# schematic.net
KiCad netlist of a schematic drawn in EAGLE
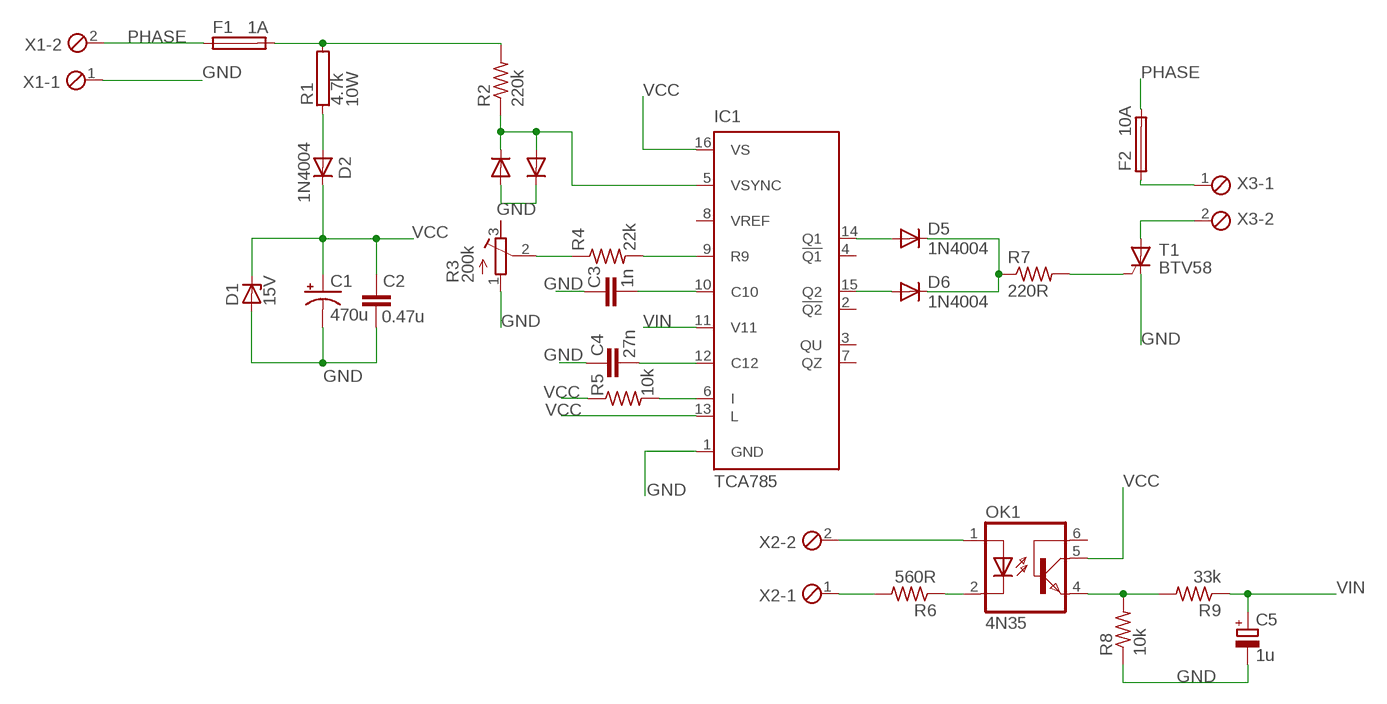
[diagram p0: schematic, sheet 1]

(export (version "E")
  (design (tool "Eeschema 10.0.6"))
  (components
    (comp (ref "C1")
      (value "470u")
      (footprint "eagle-import:E3,5-8")
      (libsource (lib "eagle-import") (part "CPOL-USE3.5-8"))
    )
    (comp (ref "C2")
      (value "0.47u")
      (footprint "eagle-import:C025-025X050")
      (libsource (lib "eagle-import") (part "C-EU025-025X050"))
    )
    (comp (ref "C3")
      (value "1n")
      (footprint "eagle-import:C025-025X050")
      (libsource (lib "eagle-import") (part "C-EU025-025X050"))
    )
    (comp (ref "C4")
      (value "27n")
      (footprint "eagle-import:C025-025X050")
      (libsource (lib "eagle-import") (part "C-EU025-025X050"))
    )
    (comp (ref "C5")
      (value "1u")
      (footprint "eagle-import:E2,5-6E")
      (libsource (lib "eagle-import") (part "CPOL-EUE2,5-6E"))
    )
    (comp (ref "D1")
      (value "15V")
      (footprint "eagle-import:F126Z12")
      (libsource (lib "eagle-import") (part "BZY97"))
    )
    (comp (ref "D2")
      (value "1N4004")
      (footprint "eagle-import:DO41-10")
      (libsource (lib "eagle-import") (part "1N4004"))
    )
    (comp (ref "D3")
      (value "1N4004")
      (footprint "eagle-import:DO41-10")
      (libsource (lib "eagle-import") (part "1N4004"))
    )
    (comp (ref "D4")
      (value "1N4004")
      (footprint "eagle-import:DO41-10")
      (libsource (lib "eagle-import") (part "1N4004"))
    )
    (comp (ref "D5")
      (value "1N4004")
      (footprint "eagle-import:DO41-10")
      (libsource (lib "eagle-import") (part "1N4004"))
    )
    (comp (ref "D6")
      (value "1N4004")
      (footprint "eagle-import:DO41-10")
      (libsource (lib "eagle-import") (part "1N4004"))
    )
    (comp (ref "F1")
      (value "1A")
      (footprint "eagle-import:SH25")
      (fields (field (name "MF") "SCHURTER") (field (name "MPN") "0031.8211"))
      (libsource (lib "eagle-import") (part "SH25"))
    )
    (comp (ref "F2")
      (value "10A")
      (footprint "eagle-import:SH25")
      (fields (field (name "MF") "SCHURTER") (field (name "MPN") "0031.8211"))
      (libsource (lib "eagle-import") (part "SH25"))
    )
    (comp (ref "IC1")
      (value "TCA785")
      (footprint "eagle-import:DIL16")
      (fields (field (name "MF") "Infineon Technologies"))
      (libsource (lib "eagle-import") (part "TCA785"))
    )
    (comp (ref "OK1")
      (value "4N35")
      (footprint "eagle-import:DIL06")
      (fields (field (name "MF") "FAIRCHILD SEMICONDUCTOR"))
      (libsource (lib "eagle-import") (part "4N35"))
    )
    (comp (ref "R1")
      (value "4.7k")
      (footprint "eagle-import:AC10")
      (fields (field (name "P") "10W"))
      (libsource (lib "eagle-import") (part "RAC10"))
    )
    (comp (ref "R2")
      (value "220k")
      (footprint "eagle-import:0207_10")
      (fields (field (name "SPICEPREFIX") "R"))
      (libsource (lib "eagle-import") (part "R-US_0207/10"))
    )
    (comp (ref "R3")
      (value "200k")
      (footprint "eagle-import:RTRIM64W")
      (libsource (lib "eagle-import") (part "R-TRIMM64W"))
    )
    (comp (ref "R4")
      (value "22k")
      (footprint "eagle-import:0207_10")
      (libsource (lib "eagle-import") (part "R-US_0207/10"))
    )
    (comp (ref "R5")
      (value "10k")
      (footprint "eagle-import:0207_15")
      (libsource (lib "eagle-import") (part "R-US_0207/15"))
    )
    (comp (ref "R6")
      (value "560R")
      (footprint "eagle-import:0204_7")
      (libsource (lib "eagle-import") (part "R-US_0204/7"))
    )
    (comp (ref "R7")
      (value "220R")
      (footprint "eagle-import:0207_15")
      (libsource (lib "eagle-import") (part "R-US_0207/15"))
    )
    (comp (ref "R8")
      (value "10k")
      (footprint "eagle-import:0207_12")
      (libsource (lib "eagle-import") (part "R-US_0207/12"))
    )
    (comp (ref "R9")
      (value "33k")
      (footprint "eagle-import:0207_12")
      (libsource (lib "eagle-import") (part "R-US_0207/12"))
    )
    (comp (ref "T1")
      (value "BTV58")
      (footprint "eagle-import:TO220CS")
      (libsource (lib "eagle-import") (part "BTV58"))
    )
    (comp (ref "X1")
      (value "MPT2")
      (footprint "eagle-import:2POL254")
      (libsource (lib "eagle-import") (part "MPT2"))
    )
    (comp (ref "X2")
      (value "MPT2")
      (footprint "eagle-import:2POL254")
      (libsource (lib "eagle-import") (part "MPT2"))
    )
    (comp (ref "X3")
      (value "MPT2")
      (footprint "eagle-import:2POL254")
      (libsource (lib "eagle-import") (part "MPT2"))
    )
  )
  (nets
    (net (code "1") (name "/GND") (class "Default")
      (node (ref "C1") (pin "-") (pinfunction "-_-") (pintype "passive"))
      (node (ref "C2") (pin "1") (pinfunction "1_1") (pintype "passive"))
      (node (ref "C3") (pin "1") (pinfunction "1_1") (pintype "passive"))
      (node (ref "C4") (pin "1") (pinfunction "1_1") (pintype "passive"))
      (node (ref "C5") (pin "-") (pinfunction "-_-") (pintype "passive"))
      (node (ref "D1") (pin "A") (pinfunction "A_A") (pintype "passive"))
      (node (ref "D3") (pin "A") (pinfunction "A_A") (pintype "passive"))
      (node (ref "D4") (pin "C") (pinfunction "C_C") (pintype "passive"))
      (node (ref "IC1") (pin "1") (pinfunction "GND_1") (pintype "power_in"))
      (node (ref "R3") (pin "1") (pinfunction "A_1") (pintype "passive"))
      (node (ref "R8") (pin "1") (pinfunction "1_1") (pintype "passive"))
      (node (ref "T1") (pin "C") (pinfunction "C_C") (pintype "passive"))
      (node (ref "X1") (pin "1") (pinfunction "1_1") (pintype "passive"))
    )
    (net (code "2") (name "/PHASE") (class "Default")
      (node (ref "F1") (pin "1") (pinfunction "1_1") (pintype "passive"))
      (node (ref "F2") (pin "2") (pinfunction "2_2") (pintype "passive"))
      (node (ref "X1") (pin "2") (pinfunction "1_2") (pintype "passive"))
    )
    (net (code "3") (name "/VCC") (class "Default")
      (node (ref "C1") (pin "+") (pinfunction "+_+") (pintype "passive"))
      (node (ref "C2") (pin "2") (pinfunction "2_2") (pintype "passive"))
      (node (ref "D1") (pin "C") (pinfunction "C_C") (pintype "passive"))
      (node (ref "D2") (pin "C") (pinfunction "C_C") (pintype "passive"))
      (node (ref "IC1") (pin "13") (pinfunction "L_13") (pintype "input"))
      (node (ref "IC1") (pin "16") (pinfunction "VS_16") (pintype "input"))
      (node (ref "OK1") (pin "5") (pinfunction "COL_5") (pintype "passive"))
      (node (ref "R5") (pin "1") (pinfunction "1_1") (pintype "passive"))
    )
    (net (code "4") (name "/VIN") (class "Default")
      (node (ref "C5") (pin "+") (pinfunction "+_+") (pintype "passive"))
      (node (ref "IC1") (pin "11") (pinfunction "V11_11") (pintype "input"))
      (node (ref "R9") (pin "1") (pinfunction "1_1") (pintype "passive"))
    )
    (net (code "5") (name "Net-(D2-PadA)") (class "Default")
      (node (ref "D2") (pin "A") (pinfunction "A_A") (pintype "passive"))
      (node (ref "R1") (pin "1") (pinfunction "1_1") (pintype "passive"))
    )
    (net (code "6") (name "Net-(D5-PadC)") (class "Default")
      (node (ref "D5") (pin "C") (pinfunction "C_C") (pintype "passive"))
      (node (ref "D6") (pin "C") (pinfunction "C_C") (pintype "passive"))
      (node (ref "R7") (pin "1") (pinfunction "1_1") (pintype "passive"))
    )
    (net (code "7") (name "Net-(F1-Pad2)") (class "Default")
      (node (ref "F1") (pin "2") (pinfunction "2_2") (pintype "passive"))
      (node (ref "R1") (pin "2") (pinfunction "2_2") (pintype "passive"))
      (node (ref "R2") (pin "2") (pinfunction "2_2") (pintype "passive"))
    )
    (net (code "8") (name "Net-(F2-Pad1)") (class "Default")
      (node (ref "F2") (pin "1") (pinfunction "1_1") (pintype "passive"))
      (node (ref "X3") (pin "1") (pinfunction "1_1") (pintype "passive"))
    )
    (net (code "9") (name "Net-(IC1-C10)") (class "Default")
      (node (ref "C3") (pin "2") (pinfunction "2_2") (pintype "passive"))
      (node (ref "IC1") (pin "10") (pinfunction "C10_10") (pintype "input"))
    )
    (net (code "10") (name "Net-(IC1-C12)") (class "Default")
      (node (ref "C4") (pin "2") (pinfunction "2_2") (pintype "passive"))
      (node (ref "IC1") (pin "12") (pinfunction "C12_12") (pintype "input"))
    )
    (net (code "11") (name "Net-(IC1-I)") (class "Default")
      (node (ref "IC1") (pin "6") (pinfunction "I_6") (pintype "input"))
      (node (ref "R5") (pin "2") (pinfunction "2_2") (pintype "passive"))
    )
    (net (code "12") (name "Net-(IC1-Q1)") (class "Default")
      (node (ref "D5") (pin "A") (pinfunction "A_A") (pintype "passive"))
      (node (ref "IC1") (pin "14") (pinfunction "Q1_14") (pintype "output"))
    )
    (net (code "13") (name "Net-(IC1-Q2)") (class "Default")
      (node (ref "D6") (pin "A") (pinfunction "A_A") (pintype "passive"))
      (node (ref "IC1") (pin "15") (pinfunction "Q2_15") (pintype "output"))
    )
    (net (code "14") (name "Net-(IC1-R9)") (class "Default")
      (node (ref "IC1") (pin "9") (pinfunction "R9_9") (pintype "input"))
      (node (ref "R4") (pin "2") (pinfunction "2_2") (pintype "passive"))
    )
    (net (code "15") (name "Net-(IC1-VSYNC)") (class "Default")
      (node (ref "D3") (pin "C") (pinfunction "C_C") (pintype "passive"))
      (node (ref "D4") (pin "A") (pinfunction "A_A") (pintype "passive"))
      (node (ref "IC1") (pin "5") (pinfunction "VSYNC_5") (pintype "input"))
      (node (ref "R2") (pin "1") (pinfunction "1_1") (pintype "passive"))
    )
    (net (code "16") (name "Net-(OK1-A)") (class "Default")
      (node (ref "OK1") (pin "1") (pinfunction "A_1") (pintype "passive"))
      (node (ref "X2") (pin "2") (pinfunction "1_2") (pintype "passive"))
    )
    (net (code "17") (name "Net-(OK1-C)") (class "Default")
      (node (ref "OK1") (pin "2") (pinfunction "C_2") (pintype "passive"))
      (node (ref "R6") (pin "1") (pinfunction "1_1") (pintype "passive"))
    )
    (net (code "18") (name "Net-(OK1-EMI)") (class "Default")
      (node (ref "OK1") (pin "4") (pinfunction "EMI_4") (pintype "passive"))
      (node (ref "R8") (pin "2") (pinfunction "2_2") (pintype "passive"))
      (node (ref "R9") (pin "2") (pinfunction "2_2") (pintype "passive"))
    )
    (net (code "19") (name "Net-(R3-S)") (class "Default")
      (node (ref "R3") (pin "2") (pinfunction "S_2") (pintype "passive"))
      (node (ref "R4") (pin "1") (pinfunction "1_1") (pintype "passive"))
    )
    (net (code "20") (name "Net-(R6-Pad2)") (class "Default")
      (node (ref "R6") (pin "2") (pinfunction "2_2") (pintype "passive"))
      (node (ref "X2") (pin "1") (pinfunction "1_1") (pintype "passive"))
    )
    (net (code "21") (name "Net-(R7-Pad2)") (class "Default")
      (node (ref "R7") (pin "2") (pinfunction "2_2") (pintype "passive"))
      (node (ref "T1") (pin "G") (pinfunction "G_G") (pintype "passive"))
    )
    (net (code "22") (name "Net-(X3B-1)") (class "Default")
      (node (ref "T1") (pin "A") (pinfunction "A_A") (pintype "passive"))
      (node (ref "X3") (pin "2") (pinfunction "1_2") (pintype "passive"))
    )
    (net (code "23") (name "unconnected-(IC1-QU-Pad3)") (class "Default")
      (node (ref "IC1") (pin "3") (pinfunction "QU_3") (pintype "output"))
    )
    (net (code "24") (name "unconnected-(IC1-QZ-Pad7)") (class "Default")
      (node (ref "IC1") (pin "7") (pinfunction "QZ_7") (pintype "output"))
    )
    (net (code "25") (name "unconnected-(IC1-VREF-Pad8)") (class "Default")
      (node (ref "IC1") (pin "8") (pinfunction "VREF_8") (pintype "input"))
    )
    (net (code "26") (name "unconnected-(IC1-~{Q1}-Pad4)") (class "Default")
      (node (ref "IC1") (pin "4") (pinfunction "~{Q1}_4") (pintype "output"))
    )
    (net (code "27") (name "unconnected-(IC1-~{Q2}-Pad2)") (class "Default")
      (node (ref "IC1") (pin "2") (pinfunction "~{Q2}_2") (pintype "output"))
    )
    (net (code "28") (name "unconnected-(OK1-BAS-Pad6)") (class "Default")
      (node (ref "OK1") (pin "6") (pinfunction "BAS_6") (pintype "passive"))
    )
    (net (code "29") (name "unconnected-(R3-E-Pad3)") (class "Default")
      (node (ref "R3") (pin "3") (pinfunction "E_3") (pintype "passive"))
    )
  )
)
